# step_down_v_reg.net
KiCad netlist of a schematic drawn in EAGLE
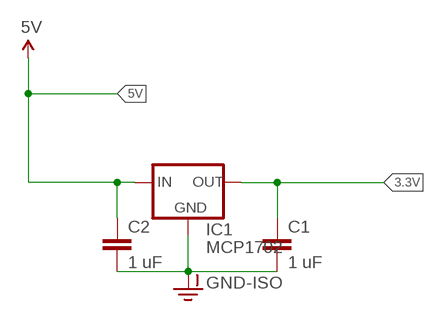
[diagram p0: schematic, sheet 1]

(export (version "E")
  (design (tool "Eeschema 10.0.6"))
  (components
    (comp (ref "C1")
      (value "1 uF")
      (footprint "eagle-import:CAP-PTH-SMALL")
      (libsource (lib "eagle-import") (part "CAPPTH"))
    )
    (comp (ref "C2")
      (value "1 uF")
      (footprint "eagle-import:CAP-PTH-SMALL")
      (libsource (lib "eagle-import") (part "CAPPTH"))
    )
    (comp (ref "IC1")
      (value "MCP1702")
      (footprint "eagle-import:TO92")
      (libsource (lib "eagle-import") (part "MCP1700TRI"))
    )
  )
  (nets
    (net (code "1") (name "3.3V") (class "Default")
      (node (ref "C1") (pin "1") (pinfunction "1_1") (pintype "passive"))
      (node (ref "IC1") (pin "3") (pinfunction "OUT_3") (pintype "passive"))
    )
    (net (code "2") (name "5V") (class "Default")
      (node (ref "C2") (pin "1") (pinfunction "1_1") (pintype "passive"))
      (node (ref "IC1") (pin "2") (pinfunction "IN_2") (pintype "input"))
    )
    (net (code "3") (name "GND-ISO") (class "Default")
      (node (ref "C1") (pin "2") (pinfunction "2_2") (pintype "passive"))
      (node (ref "C2") (pin "2") (pinfunction "2_2") (pintype "passive"))
      (node (ref "IC1") (pin "1") (pinfunction "GND_1") (pintype "input"))
    )
  )
)
